# MINI-STM32.net
KiCad netlist of a schematic drawn in Altium Designer
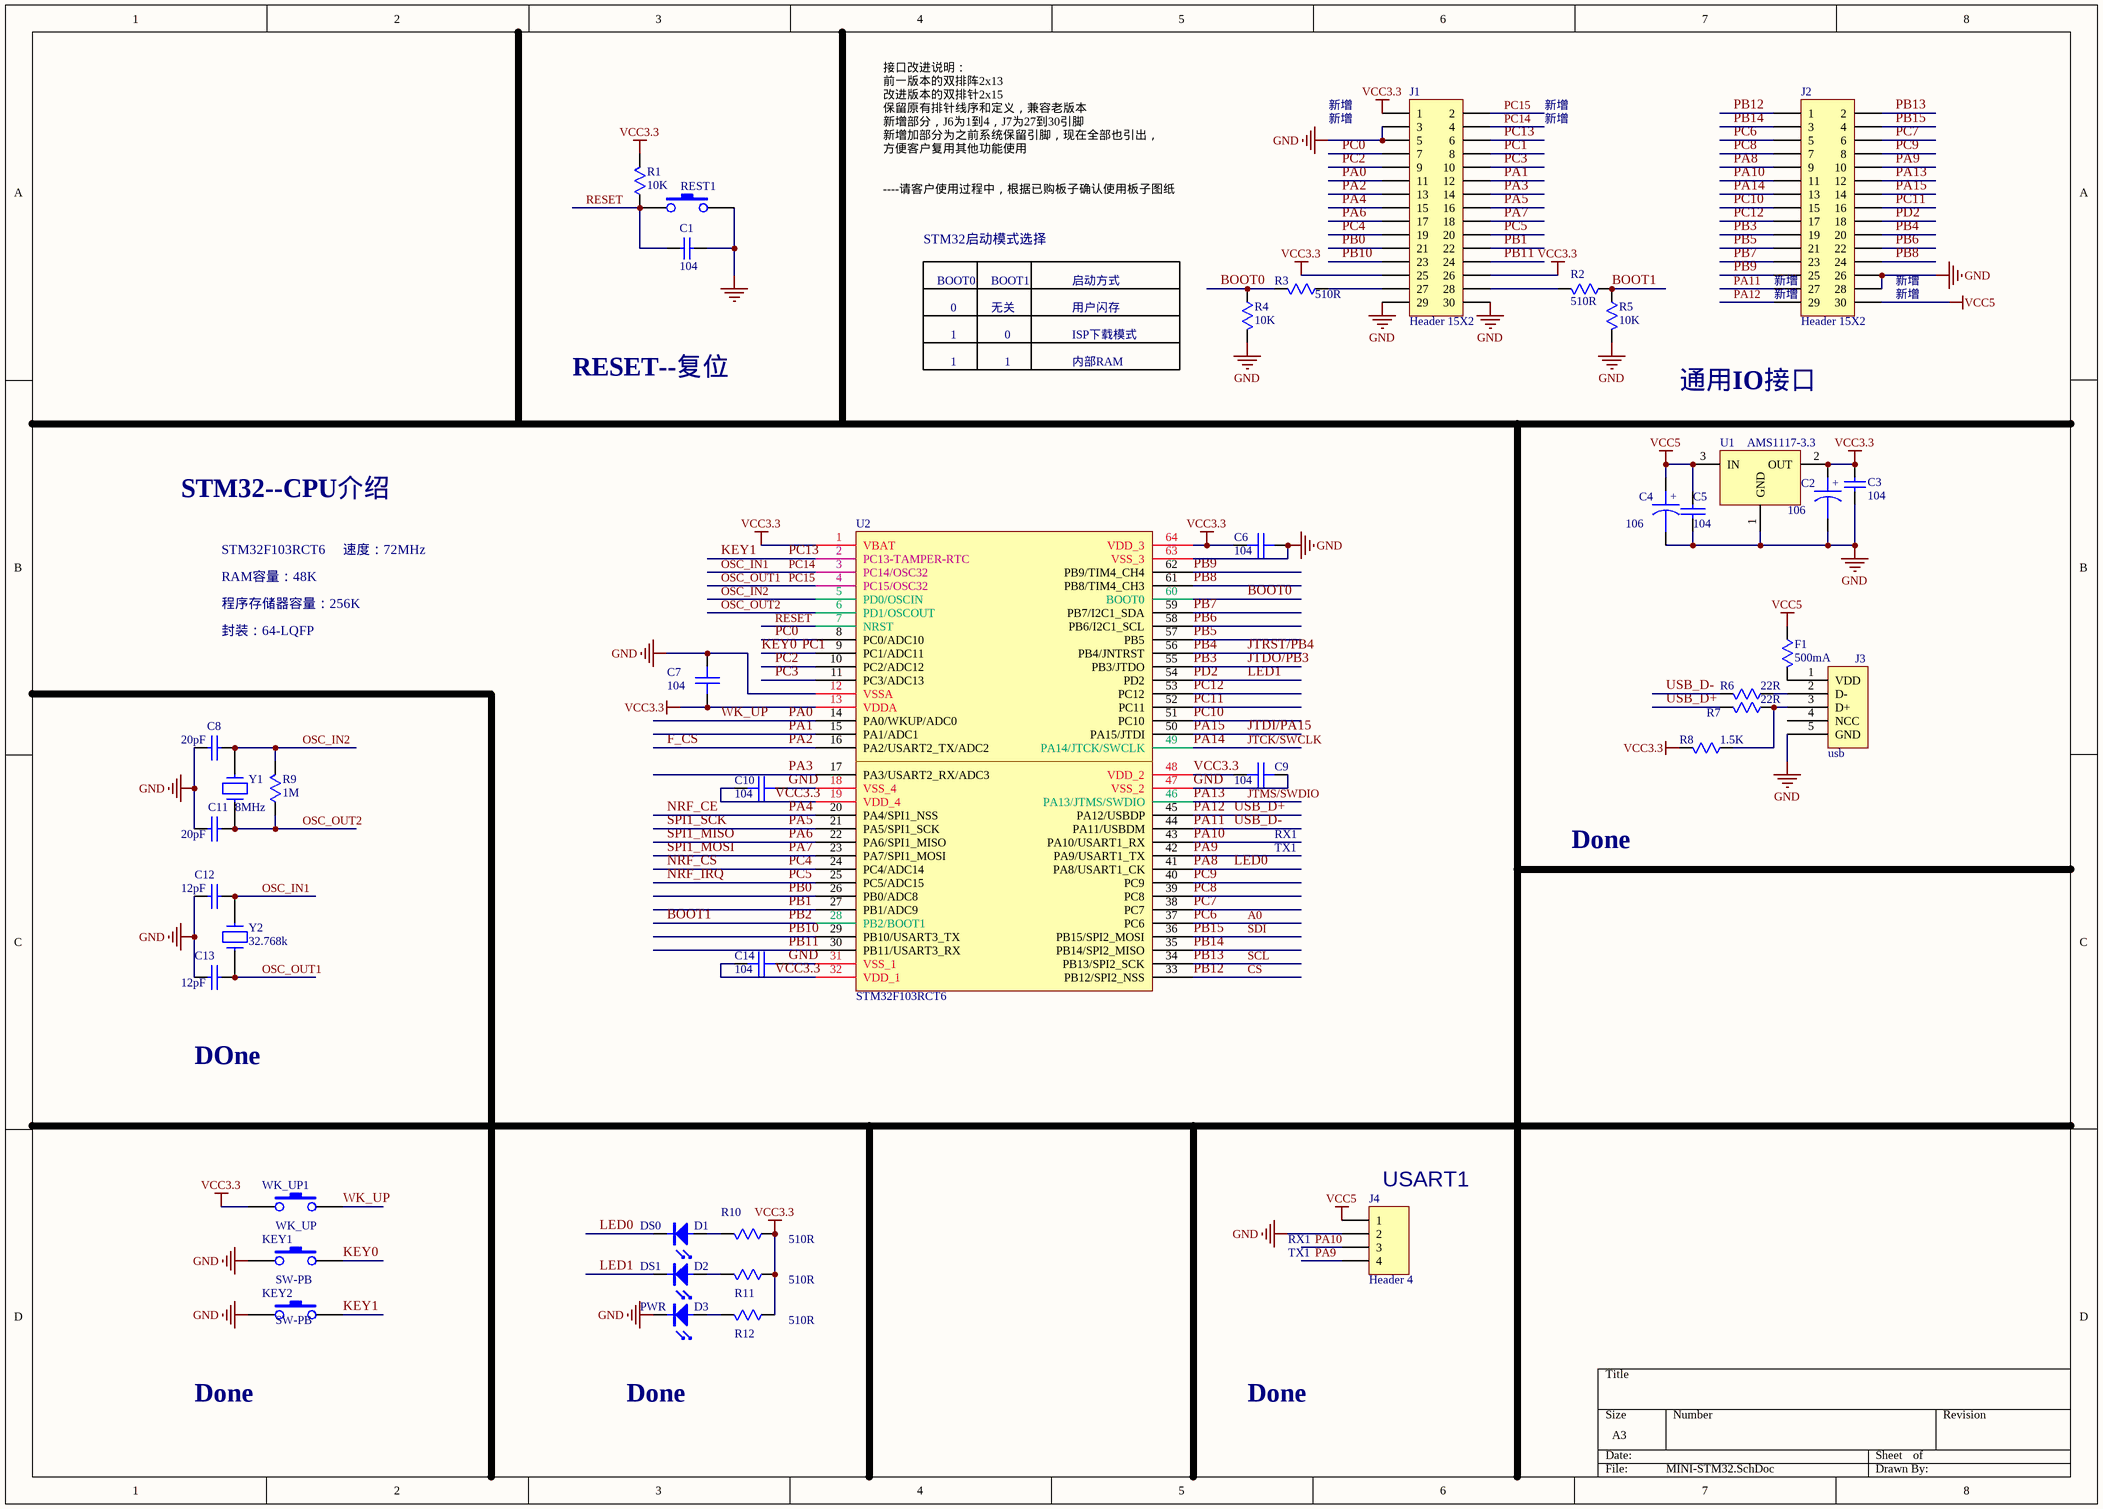
[diagram p0: MINI-STM32.SchDoc]

(export (version "E")
  (design (tool "Eeschema 10.0.6"))
  (components
    (comp (ref "C1")
      (value "104")
      (footprint "0603C")
      (description "GRM39 X7R102K50PT")
      (fields (field (name "PUBLISHER") "Altium Limited"))
      (libsource (lib "") (part "CAP_1"))
    )
    (comp (ref "C2")
      (value "106")
      (footprint "RC0805")
      (description "Capacitor")
      (libsource (lib "*") (part "CAPACITOR POL"))
    )
    (comp (ref "C3")
      (value "104")
      (footprint "0603J")
      (description "Capacitor")
      (fields (field (name "PUBLISHER") "Altium Limited"))
      (libsource (lib "*") (part "Cap"))
    )
    (comp (ref "C4")
      (value "106")
      (footprint "RC0805")
      (description "Capacitor")
      (libsource (lib "*") (part "CAPACITOR POL"))
    )
    (comp (ref "C5")
      (value "104")
      (footprint "0603J")
      (description "Capacitor")
      (libsource (lib "*") (part "CAP"))
    )
    (comp (ref "C6") (value "104") (footprint "0603J") (libsource (lib "YT1_SCH_99SE") (part "CAP")))
    (comp (ref "C7") (value "104") (footprint "0603J") (libsource (lib "YT1_SCH_99SE") (part "CAP")))
    (comp (ref "C8")
      (value "20pF")
      (footprint "0603J")
      (description "CAP CHIP 20P 50V(+-5% C0G 0603)")
      (libsource (lib "Miscellaneous Devices") (part "CAP"))
    )
    (comp (ref "C9") (value "104") (footprint "0603J") (libsource (lib "YT1_SCH_99SE") (part "CAP")))
    (comp (ref "C10") (value "104") (footprint "0603J") (libsource (lib "YT1_SCH_99SE") (part "CAP")))
    (comp (ref "C11")
      (value "20pF")
      (footprint "0603J")
      (description "CAP CHIP 20P 50V(+-5% C0G 0603)")
      (libsource (lib "Miscellaneous Devices") (part "CAP"))
    )
    (comp (ref "C12")
      (value "12pF")
      (footprint "0603J")
      (description "CAP CHIP 20P 50V(+-5% C0G 0603)")
      (libsource (lib "Miscellaneous Devices") (part "CAP"))
    )
    (comp (ref "C13")
      (value "12pF")
      (footprint "0603J")
      (description "CAP CHIP 20P 50V(+-5% C0G 0603)")
      (libsource (lib "Miscellaneous Devices") (part "CAP"))
    )
    (comp (ref "C14") (value "104") (footprint "0603J") (libsource (lib "YT1_SCH_99SE") (part "CAP")))
    (comp (ref "D1") (value "DS0") (footprint "LED0805") (libsource (lib "YT1_SCH_99SE") (part "LED")))
    (comp (ref "D2") (value "DS1") (footprint "LED0805") (libsource (lib "YT1_SCH_99SE") (part "LED")))
    (comp (ref "D3") (value "PWR") (footprint "LED0805") (libsource (lib "YT1_SCH_99SE") (part "LED")))
    (comp (ref "F1") (value "500mA") (footprint "RC0805") (libsource (lib "YT1_SCH_99SE") (part "RES")))
    (comp (ref "J1")
      (value "Header 15X2")
      (footprint "IDE15X2_2.54")
      (description "Header, 15-Pin, Dual row")
      (fields (field (name "PUBLISHER") "Altium Limited"))
      (libsource (lib "Miscellaneous Connectors") (part "Header 15X2"))
    )
    (comp (ref "J2")
      (value "Header 15X2")
      (footprint "IDE15X2_2.54")
      (description "Header, 15-Pin, Dual row")
      (fields (field (name "PUBLISHER") "Altium Limited"))
      (libsource (lib "Miscellaneous Connectors") (part "Header 15X2"))
    )
    (comp (ref "J3") (value "usb") (footprint "mini_USB") (libsource (lib "YT1_SCH_99SE") (part "usb")))
    (comp (ref "J4")
      (value "Header 4")
      (footprint "HDR1X4")
      (description "Header, 4-Pin")
      (fields (field (name "PUBLISHER") "Altium Limited"))
      (libsource (lib "Miscellaneous Connectors") (part "Header 4"))
    )
    (comp (ref "KEY1") (value "SW-PB") (footprint "SW-SPST") (libsource (lib "*") (part "SW-PB")))
    (comp (ref "KEY2") (value "SW-PB") (footprint "SW-SPST") (libsource (lib "*") (part "SW-PB")))
    (comp (ref "R1") (value "10K") (footprint "0603J") (libsource (lib "YT1_SCH_99SE") (part "RES")))
    (comp (ref "R2") (value "510R") (footprint "0603J") (libsource (lib "YT1_SCH_99SE") (part "RES")))
    (comp (ref "R3") (value "510R") (footprint "0603J") (libsource (lib "YT1_SCH_99SE") (part "RES")))
    (comp (ref "R4") (value "10K") (footprint "0603J") (libsource (lib "YT1_SCH_99SE") (part "RES")))
    (comp (ref "R5") (value "10K") (footprint "0603J") (libsource (lib "YT1_SCH_99SE") (part "RES")))
    (comp (ref "R6") (value "22R") (footprint "0603J") (libsource (lib "YT1_SCH_99SE") (part "RES")))
    (comp (ref "R7") (value "22R") (footprint "0603J") (libsource (lib "YT1_SCH_99SE") (part "RES")))
    (comp (ref "R8") (value "1.5K") (footprint "0603J") (libsource (lib "YT1_SCH_99SE") (part "RES")))
    (comp (ref "R9") (value "1M") (footprint "0603J") (libsource (lib "YT1_SCH_99SE") (part "RES")))
    (comp (ref "R10") (value "510R") (footprint "0603J") (libsource (lib "YT1_SCH_99SE") (part "RES")))
    (comp (ref "R11") (value "510R") (footprint "0603J") (libsource (lib "YT1_SCH_99SE") (part "RES")))
    (comp (ref "R12") (value "510R") (footprint "0603J") (libsource (lib "YT1_SCH_99SE") (part "RES")))
    (comp (ref "REST1") (value "~") (footprint "SW-SPST") (libsource (lib "*") (part "SW-PB")))
    (comp (ref "U1")
      (value "AMS1117-3.3")
      (footprint "SOT223")
      (libsource (lib "Newcapec9263_Board_NEW") (part "LT1085CM-3.3"))
    )
    (comp (ref "U2")
      (value "STM32F103RCT6")
      (footprint "LQFP64")
      (libsource (lib "YT1_SCH_99SE") (part "STM32F103RBT6"))
    )
    (comp (ref "WK_UP1") (value "WK_UP") (footprint "SW-SPST") (libsource (lib "*") (part "SW-PB")))
    (comp (ref "Y1")
      (value "8MHz")
      (footprint "smt-xtal")
      (description "Crystal 8MHz PLUG")
      (libsource (lib "*") (part "CRYSTAL"))
    )
    (comp (ref "Y2")
      (value "32.768k")
      (footprint "32.768k")
      (description "Crystal 8MHz PLUG")
      (libsource (lib "*") (part "CRYSTAL"))
    )
  )
  (nets
    (net (code "1") (name "/A0") (class "Default")
      (node (ref "J2") (pin "5") (pinfunction "5_5") (pintype "passive"))
      (node (ref "U2") (pin "37") (pinfunction "PC6_37") (pintype "passive"))
    )
    (net (code "2") (name "/BOOT0") (class "Default")
      (node (ref "R3") (pin "2") (pinfunction "2_2") (pintype "passive"))
      (node (ref "R4") (pin "1") (pinfunction "1_1") (pintype "passive"))
      (node (ref "U2") (pin "60") (pinfunction "BOOT0_60") (pintype "passive"))
    )
    (net (code "3") (name "/BOOT1") (class "Default")
      (node (ref "R2") (pin "1") (pinfunction "1_1") (pintype "passive"))
      (node (ref "R5") (pin "1") (pinfunction "1_1") (pintype "passive"))
      (node (ref "U2") (pin "28") (pinfunction "PB2/BOOT1_28") (pintype "passive"))
    )
    (net (code "4") (name "/CS") (class "Default")
      (node (ref "J2") (pin "1") (pinfunction "1_1") (pintype "passive"))
      (node (ref "U2") (pin "33") (pinfunction "PB12/SPI2_NSS_33") (pintype "passive"))
    )
    (net (code "5") (name "/F_CS") (class "Default")
      (node (ref "J1") (pin "13") (pinfunction "13_13") (pintype "passive"))
      (node (ref "U2") (pin "16") (pinfunction "PA2/USART2_TX/ADC2_16") (pintype "passive"))
    )
    (net (code "6") (name "/JTCK{slash}SWCLK") (class "Default")
      (node (ref "J2") (pin "13") (pinfunction "13_13") (pintype "passive"))
      (node (ref "U2") (pin "49") (pinfunction "PA14/JTCK/SWCLK_49") (pintype "passive"))
    )
    (net (code "7") (name "/JTDI{slash}PA15") (class "Default")
      (node (ref "J2") (pin "14") (pinfunction "14_14") (pintype "passive"))
      (node (ref "U2") (pin "50") (pinfunction "PA15/JTDI_50") (pintype "passive"))
    )
    (net (code "8") (name "/JTDO{slash}PB3") (class "Default")
      (node (ref "J2") (pin "19") (pinfunction "19_19") (pintype "passive"))
      (node (ref "U2") (pin "55") (pinfunction "PB3/JTDO_55") (pintype "passive"))
    )
    (net (code "9") (name "/JTMS{slash}SWDIO") (class "Default")
      (node (ref "J2") (pin "12") (pinfunction "12_12") (pintype "passive"))
      (node (ref "U2") (pin "46") (pinfunction "PA13/JTMS/SWDIO_46") (pintype "passive"))
    )
    (net (code "10") (name "/JTRST{slash}PB4") (class "Default")
      (node (ref "J2") (pin "20") (pinfunction "20_20") (pintype "passive"))
      (node (ref "U2") (pin "56") (pinfunction "PB4/JNTRST_56") (pintype "passive"))
    )
    (net (code "11") (name "/KEY0") (class "Default")
      (node (ref "J1") (pin "8") (pinfunction "8_8") (pintype "passive"))
      (node (ref "KEY1") (pin "2") (pinfunction "2_2") (pintype "passive"))
      (node (ref "U2") (pin "9") (pinfunction "PC1/ADC11_9") (pintype "passive"))
    )
    (net (code "12") (name "/KEY1") (class "Default")
      (node (ref "J1") (pin "6") (pinfunction "6_6") (pintype "passive"))
      (node (ref "KEY2") (pin "2") (pinfunction "2_2") (pintype "passive"))
      (node (ref "U2") (pin "2") (pinfunction "PC13-TAMPER-RTC_2") (pintype "passive"))
    )
    (net (code "13") (name "/LED0") (class "Default")
      (node (ref "D1") (pin "2") (pinfunction "2_2") (pintype "passive"))
      (node (ref "J2") (pin "9") (pinfunction "9_9") (pintype "passive"))
      (node (ref "U2") (pin "41") (pinfunction "PA8/USART1_CK_41") (pintype "passive"))
    )
    (net (code "14") (name "/LED1") (class "Default")
      (node (ref "D2") (pin "2") (pinfunction "2_2") (pintype "passive"))
      (node (ref "J2") (pin "18") (pinfunction "18_18") (pintype "passive"))
      (node (ref "U2") (pin "54") (pinfunction "PD2_54") (pintype "passive"))
    )
    (net (code "15") (name "/NRF_CE") (class "Default")
      (node (ref "J1") (pin "15") (pinfunction "15_15") (pintype "passive"))
      (node (ref "U2") (pin "20") (pinfunction "PA4/SPI1_NSS_20") (pintype "passive"))
    )
    (net (code "16") (name "/NRF_CS") (class "Default")
      (node (ref "J1") (pin "19") (pinfunction "19_19") (pintype "passive"))
      (node (ref "U2") (pin "24") (pinfunction "PC4/ADC14_24") (pintype "passive"))
    )
    (net (code "17") (name "/NRF_IRQ") (class "Default")
      (node (ref "J1") (pin "20") (pinfunction "20_20") (pintype "passive"))
      (node (ref "U2") (pin "25") (pinfunction "PC5/ADC15_25") (pintype "passive"))
    )
    (net (code "18") (name "/OSC_IN1") (class "Default")
      (node (ref "C12") (pin "2") (pinfunction "2_2") (pintype "passive"))
      (node (ref "J1") (pin "4") (pinfunction "4_4") (pintype "passive"))
      (node (ref "U2") (pin "3") (pinfunction "PC14/OSC32_3") (pintype "passive"))
      (node (ref "Y2") (pin "2") (pinfunction "2_2") (pintype "passive"))
    )
    (net (code "19") (name "/OSC_IN2") (class "Default")
      (node (ref "C8") (pin "2") (pinfunction "2_2") (pintype "passive"))
      (node (ref "R9") (pin "2") (pinfunction "2_2") (pintype "passive"))
      (node (ref "U2") (pin "5") (pinfunction "PD0/OSCIN_5") (pintype "passive"))
      (node (ref "Y1") (pin "1") (pinfunction "1_1") (pintype "passive"))
    )
    (net (code "20") (name "/OSC_OUT1") (class "Default")
      (node (ref "C13") (pin "2") (pinfunction "2_2") (pintype "passive"))
      (node (ref "J1") (pin "2") (pinfunction "2_2") (pintype "passive"))
      (node (ref "U2") (pin "4") (pinfunction "PC15/OSC32_4") (pintype "passive"))
      (node (ref "Y2") (pin "1") (pinfunction "1_1") (pintype "passive"))
    )
    (net (code "21") (name "/OSC_OUT2") (class "Default")
      (node (ref "C11") (pin "2") (pinfunction "2_2") (pintype "passive"))
      (node (ref "R9") (pin "1") (pinfunction "1_1") (pintype "passive"))
      (node (ref "U2") (pin "6") (pinfunction "PD1/OSCOUT_6") (pintype "passive"))
      (node (ref "Y1") (pin "2") (pinfunction "2_2") (pintype "passive"))
    )
    (net (code "22") (name "/PA0") (class "Default")
      (node (ref "J1") (pin "11") (pinfunction "11_11") (pintype "passive"))
      (node (ref "U2") (pin "14") (pinfunction "PA0/WKUP/ADC0_14") (pintype "passive"))
      (node (ref "WK_UP1") (pin "2") (pinfunction "2_2") (pintype "passive"))
    )
    (net (code "23") (name "/PA1") (class "Default")
      (node (ref "J1") (pin "12") (pinfunction "12_12") (pintype "passive"))
      (node (ref "U2") (pin "15") (pinfunction "PA1/ADC1_15") (pintype "passive"))
    )
    (net (code "24") (name "/PA3") (class "Default")
      (node (ref "J1") (pin "14") (pinfunction "14_14") (pintype "passive"))
      (node (ref "U2") (pin "17") (pinfunction "PA3/USART2_RX/ADC3_17") (pintype "passive"))
    )
    (net (code "25") (name "/PA5") (class "Default")
      (node (ref "J1") (pin "16") (pinfunction "16_16") (pintype "passive"))
      (node (ref "U2") (pin "21") (pinfunction "PA5/SPI1_SCK_21") (pintype "passive"))
    )
    (net (code "26") (name "/PA6") (class "Default")
      (node (ref "J1") (pin "17") (pinfunction "17_17") (pintype "passive"))
      (node (ref "U2") (pin "22") (pinfunction "PA6/SPI1_MISO_22") (pintype "passive"))
    )
    (net (code "27") (name "/PA7") (class "Default")
      (node (ref "J1") (pin "18") (pinfunction "18_18") (pintype "passive"))
      (node (ref "U2") (pin "23") (pinfunction "PA7/SPI1_MOSI_23") (pintype "passive"))
    )
    (net (code "28") (name "/PA9") (class "Default")
      (node (ref "J2") (pin "10") (pinfunction "10_10") (pintype "passive"))
      (node (ref "J4") (pin "4") (pinfunction "4_4") (pintype "passive"))
      (node (ref "U2") (pin "42") (pinfunction "PA9/USART1_TX_42") (pintype "passive"))
    )
    (net (code "29") (name "/PA10") (class "Default")
      (node (ref "J2") (pin "11") (pinfunction "11_11") (pintype "passive"))
      (node (ref "J4") (pin "3") (pinfunction "3_3") (pintype "passive"))
      (node (ref "U2") (pin "43") (pinfunction "PA10/USART1_RX_43") (pintype "passive"))
    )
    (net (code "30") (name "/PA11") (class "Default")
      (node (ref "J2") (pin "27") (pinfunction "27_27") (pintype "passive"))
      (node (ref "R6") (pin "2") (pinfunction "2_2") (pintype "passive"))
      (node (ref "U2") (pin "44") (pinfunction "PA11/USBDM_44") (pintype "passive"))
    )
    (net (code "31") (name "/PA12") (class "Default")
      (node (ref "J2") (pin "29") (pinfunction "29_29") (pintype "passive"))
      (node (ref "R7") (pin "2") (pinfunction "2_2") (pintype "passive"))
      (node (ref "U2") (pin "45") (pinfunction "PA12/USBDP_45") (pintype "passive"))
    )
    (net (code "32") (name "/PB0") (class "Default")
      (node (ref "J1") (pin "21") (pinfunction "21_21") (pintype "passive"))
      (node (ref "U2") (pin "26") (pinfunction "PB0/ADC8_26") (pintype "passive"))
    )
    (net (code "33") (name "/PB1") (class "Default")
      (node (ref "J1") (pin "22") (pinfunction "22_22") (pintype "passive"))
      (node (ref "U2") (pin "27") (pinfunction "PB1/ADC9_27") (pintype "passive"))
    )
    (net (code "34") (name "/PB5") (class "Default")
      (node (ref "J2") (pin "21") (pinfunction "21_21") (pintype "passive"))
      (node (ref "U2") (pin "57") (pinfunction "PB5_57") (pintype "passive"))
    )
    (net (code "35") (name "/PB6") (class "Default")
      (node (ref "J2") (pin "22") (pinfunction "22_22") (pintype "passive"))
      (node (ref "U2") (pin "58") (pinfunction "PB6/I2C1_SCL_58") (pintype "passive"))
    )
    (net (code "36") (name "/PB7") (class "Default")
      (node (ref "J2") (pin "23") (pinfunction "23_23") (pintype "passive"))
      (node (ref "U2") (pin "59") (pinfunction "PB7/I2C1_SDA_59") (pintype "passive"))
    )
    (net (code "37") (name "/PB8") (class "Default")
      (node (ref "J2") (pin "24") (pinfunction "24_24") (pintype "passive"))
      (node (ref "U2") (pin "61") (pinfunction "PB8/TIM4_CH3_61") (pintype "passive"))
    )
    (net (code "38") (name "/PB9") (class "Default")
      (node (ref "J2") (pin "25") (pinfunction "25_25") (pintype "passive"))
      (node (ref "U2") (pin "62") (pinfunction "PB9/TIM4_CH4_62") (pintype "passive"))
    )
    (net (code "39") (name "/PB10") (class "Default")
      (node (ref "J1") (pin "23") (pinfunction "23_23") (pintype "passive"))
      (node (ref "U2") (pin "29") (pinfunction "PB10/USART3_TX_29") (pintype "passive"))
    )
    (net (code "40") (name "/PB11") (class "Default")
      (node (ref "J1") (pin "24") (pinfunction "24_24") (pintype "passive"))
      (node (ref "U2") (pin "30") (pinfunction "PB11/USART3_RX_30") (pintype "passive"))
    )
    (net (code "41") (name "/PB13") (class "Default")
      (node (ref "J2") (pin "2") (pinfunction "2_2") (pintype "passive"))
      (node (ref "U2") (pin "34") (pinfunction "PB13/SPI2_SCK_34") (pintype "passive"))
    )
    (net (code "42") (name "/PB14") (class "Default")
      (node (ref "J2") (pin "3") (pinfunction "3_3") (pintype "passive"))
      (node (ref "U2") (pin "35") (pinfunction "PB14/SPI2_MISO_35") (pintype "passive"))
    )
    (net (code "43") (name "/PB15") (class "Default")
      (node (ref "J2") (pin "4") (pinfunction "4_4") (pintype "passive"))
      (node (ref "U2") (pin "36") (pinfunction "PB15/SPI2_MOSI_36") (pintype "passive"))
    )
    (net (code "44") (name "/PC0") (class "Default")
      (node (ref "J1") (pin "7") (pinfunction "7_7") (pintype "passive"))
      (node (ref "U2") (pin "8") (pinfunction "PC0/ADC10_8") (pintype "passive"))
    )
    (net (code "45") (name "/PC2") (class "Default")
      (node (ref "J1") (pin "9") (pinfunction "9_9") (pintype "passive"))
      (node (ref "U2") (pin "10") (pinfunction "PC2/ADC12_10") (pintype "passive"))
    )
    (net (code "46") (name "/PC3") (class "Default")
      (node (ref "J1") (pin "10") (pinfunction "10_10") (pintype "passive"))
      (node (ref "U2") (pin "11") (pinfunction "PC3/ADC13_11") (pintype "passive"))
    )
    (net (code "47") (name "/PC7") (class "Default")
      (node (ref "J2") (pin "6") (pinfunction "6_6") (pintype "passive"))
      (node (ref "U2") (pin "38") (pinfunction "PC7_38") (pintype "passive"))
    )
    (net (code "48") (name "/PC8") (class "Default")
      (node (ref "J2") (pin "7") (pinfunction "7_7") (pintype "passive"))
      (node (ref "U2") (pin "39") (pinfunction "PC8_39") (pintype "passive"))
    )
    (net (code "49") (name "/PC9") (class "Default")
      (node (ref "J2") (pin "8") (pinfunction "8_8") (pintype "passive"))
      (node (ref "U2") (pin "40") (pinfunction "PC9_40") (pintype "passive"))
    )
    (net (code "50") (name "/PC10") (class "Default")
      (node (ref "J2") (pin "15") (pinfunction "15_15") (pintype "passive"))
      (node (ref "U2") (pin "51") (pinfunction "PC10_51") (pintype "passive"))
    )
    (net (code "51") (name "/PC11") (class "Default")
      (node (ref "J2") (pin "16") (pinfunction "16_16") (pintype "passive"))
      (node (ref "U2") (pin "52") (pinfunction "PC11_52") (pintype "passive"))
    )
    (net (code "52") (name "/PC12") (class "Default")
      (node (ref "J2") (pin "17") (pinfunction "17_17") (pintype "passive"))
      (node (ref "U2") (pin "53") (pinfunction "PC12_53") (pintype "passive"))
    )
    (net (code "53") (name "/RESET") (class "Default")
      (node (ref "C1") (pin "2") (pinfunction "2_2") (pintype "passive"))
      (node (ref "R1") (pin "1") (pinfunction "1_1") (pintype "passive"))
      (node (ref "REST1") (pin "1") (pinfunction "1_1") (pintype "passive"))
      (node (ref "U2") (pin "7") (pinfunction "NRST_7") (pintype "passive"))
    )
    (net (code "54") (name "GND") (class "Default")
      (node (ref "C1") (pin "1") (pinfunction "1_1") (pintype "passive"))
      (node (ref "C10") (pin "2") (pinfunction "2_2") (pintype "passive"))
      (node (ref "C11") (pin "1") (pinfunction "1_1") (pintype "passive"))
      (node (ref "C12") (pin "1") (pinfunction "1_1") (pintype "passive"))
      (node (ref "C13") (pin "1") (pinfunction "1_1") (pintype "passive"))
      (node (ref "C14") (pin "2") (pinfunction "2_2") (pintype "passive"))
      (node (ref "C2") (pin "2") (pinfunction "2_2") (pintype "passive"))
      (node (ref "C3") (pin "2") (pinfunction "2_2") (pintype "passive"))
      (node (ref "C4") (pin "2") (pinfunction "2_2") (pintype "passive"))
      (node (ref "C5") (pin "2") (pinfunction "2_2") (pintype "passive"))
      (node (ref "C6") (pin "2") (pinfunction "2_2") (pintype "passive"))
      (node (ref "C7") (pin "1") (pinfunction "1_1") (pintype "passive"))
      (node (ref "C8") (pin "1") (pinfunction "1_1") (pintype "passive"))
      (node (ref "C9") (pin "2") (pinfunction "2_2") (pintype "passive"))
      (node (ref "D3") (pin "2") (pinfunction "2_2") (pintype "passive"))
      (node (ref "J1") (pin "29") (pinfunction "29_29") (pintype "passive"))
      (node (ref "J1") (pin "3") (pinfunction "3_3") (pintype "passive"))
      (node (ref "J1") (pin "30") (pinfunction "30_30") (pintype "passive"))
      (node (ref "J1") (pin "5") (pinfunction "5_5") (pintype "passive"))
      (node (ref "J2") (pin "26") (pinfunction "26_26") (pintype "passive"))
      (node (ref "J2") (pin "28") (pinfunction "28_28") (pintype "passive"))
      (node (ref "J3") (pin "5") (pinfunction "GND_5") (pintype "passive"))
      (node (ref "J4") (pin "2") (pinfunction "2_2") (pintype "passive"))
      (node (ref "KEY1") (pin "1") (pinfunction "1_1") (pintype "passive"))
      (node (ref "KEY2") (pin "1") (pinfunction "1_1") (pintype "passive"))
      (node (ref "R4") (pin "2") (pinfunction "2_2") (pintype "passive"))
      (node (ref "R5") (pin "2") (pinfunction "2_2") (pintype "passive"))
      (node (ref "REST1") (pin "2") (pinfunction "2_2") (pintype "passive"))
      (node (ref "U1") (pin "1") (pinfunction "GND_1") (pintype "passive"))
      (node (ref "U2") (pin "12") (pinfunction "VSSA_12") (pintype "passive"))
      (node (ref "U2") (pin "18") (pinfunction "VSS_4_18") (pintype "passive"))
      (node (ref "U2") (pin "31") (pinfunction "VSS_1_31") (pintype "passive"))
      (node (ref "U2") (pin "47") (pinfunction "VSS_2_47") (pintype "passive"))
      (node (ref "U2") (pin "63") (pinfunction "VSS_3_63") (pintype "passive"))
    )
    (net (code "55") (name "Net-(D1-Pad1)") (class "Default")
      (node (ref "D1") (pin "1") (pinfunction "1_1") (pintype "passive"))
      (node (ref "R10") (pin "2") (pinfunction "2_2") (pintype "passive"))
    )
    (net (code "56") (name "Net-(D2-Pad1)") (class "Default")
      (node (ref "D2") (pin "1") (pinfunction "1_1") (pintype "passive"))
      (node (ref "R11") (pin "2") (pinfunction "2_2") (pintype "passive"))
    )
    (net (code "57") (name "Net-(D3-Pad1)") (class "Default")
      (node (ref "D3") (pin "1") (pinfunction "1_1") (pintype "passive"))
      (node (ref "R12") (pin "2") (pinfunction "2_2") (pintype "passive"))
    )
    (net (code "58") (name "Net-(J1-Pad27)") (class "Default")
      (node (ref "J1") (pin "27") (pinfunction "27_27") (pintype "passive"))
      (node (ref "R3") (pin "1") (pinfunction "1_1") (pintype "passive"))
    )
    (net (code "59") (name "Net-(J1-Pad28)") (class "Default")
      (node (ref "J1") (pin "28") (pinfunction "28_28") (pintype "passive"))
      (node (ref "R2") (pin "2") (pinfunction "2_2") (pintype "passive"))
    )
    (net (code "60") (name "Net-(J3-D+)") (class "Default")
      (node (ref "J3") (pin "3") (pinfunction "D+_3") (pintype "passive"))
      (node (ref "R7") (pin "1") (pinfunction "1_1") (pintype "passive"))
      (node (ref "R8") (pin "1") (pinfunction "1_1") (pintype "passive"))
    )
    (net (code "61") (name "Net-(J3-D-)") (class "Default")
      (node (ref "J3") (pin "2") (pinfunction "D-_2") (pintype "passive"))
      (node (ref "R6") (pin "1") (pinfunction "1_1") (pintype "passive"))
    )
    (net (code "62") (name "Net-(J3-VDD)") (class "Default")
      (node (ref "F1") (pin "2") (pinfunction "2_2") (pintype "passive"))
      (node (ref "J3") (pin "1") (pinfunction "VDD_1") (pintype "passive"))
    )
    (net (code "63") (name "VCC3.3") (class "Default")
      (node (ref "C10") (pin "1") (pinfunction "1_1") (pintype "passive"))
      (node (ref "C14") (pin "1") (pinfunction "1_1") (pintype "passive"))
      (node (ref "C2") (pin "1") (pinfunction "1_1") (pintype "passive"))
      (node (ref "C3") (pin "1") (pinfunction "1_1") (pintype "passive"))
      (node (ref "C6") (pin "1") (pinfunction "1_1") (pintype "passive"))
      (node (ref "C7") (pin "2") (pinfunction "2_2") (pintype "passive"))
      (node (ref "C9") (pin "1") (pinfunction "1_1") (pintype "passive"))
      (node (ref "J1") (pin "1") (pinfunction "1_1") (pintype "passive"))
      (node (ref "J1") (pin "25") (pinfunction "25_25") (pintype "passive"))
      (node (ref "J1") (pin "26") (pinfunction "26_26") (pintype "passive"))
      (node (ref "R1") (pin "2") (pinfunction "2_2") (pintype "passive"))
      (node (ref "R10") (pin "1") (pinfunction "1_1") (pintype "passive"))
      (node (ref "R11") (pin "1") (pinfunction "1_1") (pintype "passive"))
      (node (ref "R12") (pin "1") (pinfunction "1_1") (pintype "passive"))
      (node (ref "R8") (pin "2") (pinfunction "2_2") (pintype "passive"))
      (node (ref "U1") (pin "2") (pinfunction "OUT_2") (pintype "passive"))
      (node (ref "U2") (pin "1") (pinfunction "VBAT_1") (pintype "passive"))
      (node (ref "U2") (pin "13") (pinfunction "VDDA_13") (pintype "passive"))
      (node (ref "U2") (pin "19") (pinfunction "VDD_4_19") (pintype "passive"))
      (node (ref "U2") (pin "32") (pinfunction "VDD_1_32") (pintype "passive"))
      (node (ref "U2") (pin "48") (pinfunction "VDD_2_48") (pintype "passive"))
      (node (ref "U2") (pin "64") (pinfunction "VDD_3_64") (pintype "passive"))
      (node (ref "WK_UP1") (pin "1") (pinfunction "1_1") (pintype "passive"))
    )
    (net (code "64") (name "VCC5") (class "Default")
      (node (ref "C4") (pin "1") (pinfunction "1_1") (pintype "passive"))
      (node (ref "C5") (pin "1") (pinfunction "1_1") (pintype "passive"))
      (node (ref "F1") (pin "1") (pinfunction "1_1") (pintype "passive"))
      (node (ref "J2") (pin "30") (pinfunction "30_30") (pintype "passive"))
      (node (ref "J4") (pin "1") (pinfunction "1_1") (pintype "passive"))
      (node (ref "U1") (pin "3") (pinfunction "IN_3") (pintype "passive"))
    )
    (net (code "65") (name "unconnected-(J3-NCC-Pad4)") (class "Default")
      (node (ref "J3") (pin "4") (pinfunction "NCC_4") (pintype "passive"))
    )
  )
)
